# PiShutdownButton.net
KiCad netlist of a schematic drawn in EAGLE
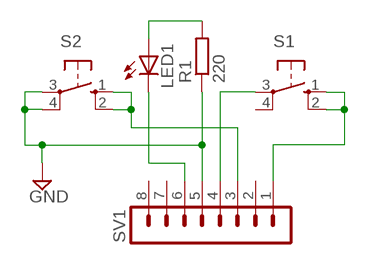
[diagram p0: schematic, sheet 1]

(export (version "E")
  (design (tool "Eeschema 10.0.6"))
  (components
    (comp (ref "LED1")
      (value "LED3MM")
      (footprint "eagle-import:LED3MM")
      (libsource (lib "eagle-import") (part "LED3MM"))
    )
    (comp (ref "R1")
      (value "220")
      (footprint "eagle-import:0204_5")
      (libsource (lib "eagle-import") (part "R-EU_0204/5"))
    )
    (comp (ref "S1")
      (value "10-XX")
      (footprint "eagle-import:B3F-10XX")
      (fields (field (name "MPN") "B3F-1000"))
      (libsource (lib "eagle-import") (part "10-XX"))
    )
    (comp (ref "S2")
      (value "10-XX")
      (footprint "eagle-import:B3F-10XX")
      (fields (field (name "MPN") "B3F-1000"))
      (libsource (lib "eagle-import") (part "10-XX"))
    )
    (comp (ref "SV1")
      (value "MA08-1")
      (footprint "eagle-import:MA08-1")
      (libsource (lib "eagle-import") (part "MA08-1"))
    )
  )
  (nets
    (net (code "1") (name "GND") (class "Default")
      (node (ref "R1") (pin "1") (pinfunction "1_1") (pintype "passive"))
      (node (ref "S2") (pin "3") (pinfunction "P_3") (pintype "passive"))
      (node (ref "S2") (pin "4") (pinfunction "P1_4") (pintype "passive"))
      (node (ref "SV1") (pin "5") (pinfunction "5_5") (pintype "passive"))
    )
    (net (code "2") (name "Net-(LED1-C)") (class "Default")
      (node (ref "LED1") (pin "K") (pinfunction "C_K") (pintype "passive"))
      (node (ref "SV1") (pin "6") (pinfunction "6_6") (pintype "passive"))
    )
    (net (code "3") (name "Net-(LED1-PadA)") (class "Default")
      (node (ref "LED1") (pin "A") (pinfunction "A_A") (pintype "passive"))
      (node (ref "R1") (pin "2") (pinfunction "2_2") (pintype "passive"))
    )
    (net (code "4") (name "Net-(S1-P)") (class "Default")
      (node (ref "S1") (pin "3") (pinfunction "P_3") (pintype "passive"))
      (node (ref "SV1") (pin "4") (pinfunction "4_4") (pintype "passive"))
    )
    (net (code "5") (name "Net-(S1-S)") (class "Default")
      (node (ref "S1") (pin "1") (pinfunction "S_1") (pintype "passive"))
      (node (ref "S1") (pin "2") (pinfunction "S1_2") (pintype "passive"))
      (node (ref "SV1") (pin "1") (pinfunction "1_1") (pintype "passive"))
    )
    (net (code "6") (name "Net-(S2-S)") (class "Default")
      (node (ref "S2") (pin "1") (pinfunction "S_1") (pintype "passive"))
      (node (ref "S2") (pin "2") (pinfunction "S1_2") (pintype "passive"))
      (node (ref "SV1") (pin "3") (pinfunction "3_3") (pintype "passive"))
    )
    (net (code "7") (name "unconnected-(S1-P1-Pad4)") (class "Default")
      (node (ref "S1") (pin "4") (pinfunction "P1_4") (pintype "passive"))
    )
    (net (code "8") (name "unconnected-(SV1-Pad2)") (class "Default")
      (node (ref "SV1") (pin "2") (pinfunction "2_2") (pintype "passive"))
    )
    (net (code "9") (name "unconnected-(SV1-Pad7)") (class "Default")
      (node (ref "SV1") (pin "7") (pinfunction "7_7") (pintype "passive"))
    )
    (net (code "10") (name "unconnected-(SV1-Pad8)") (class "Default")
      (node (ref "SV1") (pin "8") (pinfunction "8_8") (pintype "passive"))
    )
  )
)
